# FishCaller.net
KiCad netlist of a schematic drawn in EAGLE
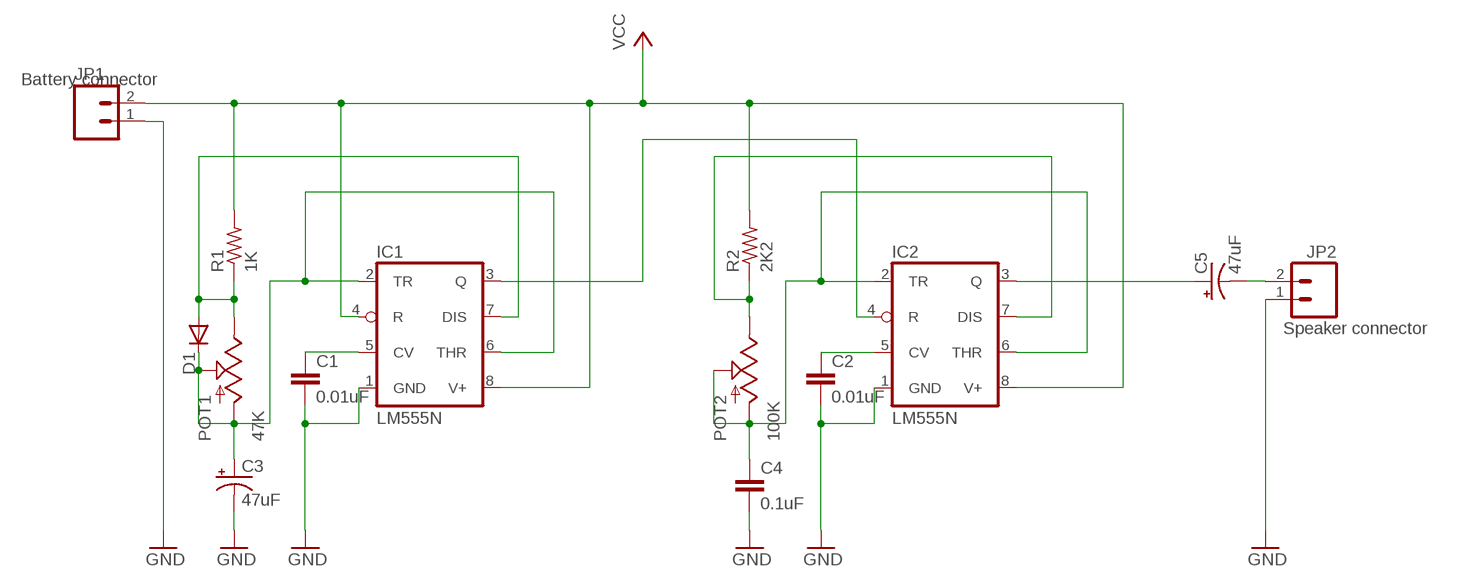
[diagram p0: schematic, sheet 1]

(export (version "E")
  (design (tool "Eeschema 10.0.6"))
  (components
    (comp (ref "C1")
      (value "0.01uF")
      (footprint "eagle-import:CAP-PTH-SMALL")
      (libsource (lib "eagle-import") (part "CAPPTH"))
    )
    (comp (ref "C2")
      (value "0.01uF")
      (footprint "eagle-import:CAP-PTH-SMALL")
      (libsource (lib "eagle-import") (part "CAPPTH"))
    )
    (comp (ref "C3")
      (value "47uF")
      (footprint "eagle-import:E2,5-6")
      (libsource (lib "eagle-import") (part "CPOL-USE2.5-6"))
    )
    (comp (ref "C4")
      (value "0.1uF")
      (footprint "eagle-import:CAP-PTH-SMALL")
      (libsource (lib "eagle-import") (part "CAPPTH"))
    )
    (comp (ref "C5")
      (value "47uF")
      (footprint "eagle-import:E2,5-6")
      (libsource (lib "eagle-import") (part "CPOL-USE2.5-6"))
    )
    (comp (ref "D1")
      (value "DIODE1N4148")
      (footprint "eagle-import:DIODE-1N4148")
      (libsource (lib "eagle-import") (part "DIODE1N4148"))
    )
    (comp (ref "IC1")
      (value "LM555N")
      (footprint "eagle-import:DIL08-ROUND")
      (libsource (lib "eagle-import") (part "555NLM"))
    )
    (comp (ref "IC2")
      (value "LM555N")
      (footprint "eagle-import:DIL08-ROUND")
      (libsource (lib "eagle-import") (part "555NLM"))
    )
    (comp (ref "JP1")
      (value "M02")
      (footprint "eagle-import:1X02_LONGPADS")
      (libsource (lib "eagle-import") (part "M02"))
    )
    (comp (ref "JP2")
      (value "M02")
      (footprint "eagle-import:1X02_LONGPADS")
      (libsource (lib "eagle-import") (part "M02"))
    )
    (comp (ref "POT1")
      (value "47K")
      (footprint "eagle-import:ALPS_POT")
      (libsource (lib "eagle-import") (part "POT"))
    )
    (comp (ref "POT2")
      (value "100K")
      (footprint "eagle-import:ALPS_POT")
      (libsource (lib "eagle-import") (part "POT"))
    )
    (comp (ref "R1")
      (value "1K")
      (footprint "eagle-import:0207_9")
      (libsource (lib "eagle-import") (part "R-US_0207/9"))
    )
    (comp (ref "R2")
      (value "2K2")
      (footprint "eagle-import:0207_9")
      (libsource (lib "eagle-import") (part "R-US_0207/9"))
    )
  )
  (nets
    (net (code "1") (name "GND") (class "Default")
      (node (ref "C1") (pin "2") (pinfunction "2_2") (pintype "passive"))
      (node (ref "C2") (pin "2") (pinfunction "2_2") (pintype "passive"))
      (node (ref "C3") (pin "-") (pinfunction "-_-") (pintype "passive"))
      (node (ref "C4") (pin "2") (pinfunction "2_2") (pintype "passive"))
      (node (ref "IC1") (pin "1") (pinfunction "GND_1") (pintype "power_in"))
      (node (ref "IC2") (pin "1") (pinfunction "GND_1") (pintype "power_in"))
      (node (ref "JP1") (pin "1") (pinfunction "1_1") (pintype "passive"))
      (node (ref "JP2") (pin "1") (pinfunction "1_1") (pintype "passive"))
    )
    (net (code "2") (name "Net-(C5-Pad-)") (class "Default")
      (node (ref "C5") (pin "-") (pinfunction "-_-") (pintype "passive"))
      (node (ref "JP2") (pin "2") (pinfunction "2_2") (pintype "passive"))
    )
    (net (code "3") (name "Net-(IC1-CV)") (class "Default")
      (node (ref "C1") (pin "1") (pinfunction "1_1") (pintype "passive"))
      (node (ref "IC1") (pin "5") (pinfunction "CV_5") (pintype "input"))
    )
    (net (code "4") (name "Net-(IC1-DIS)") (class "Default")
      (node (ref "D1") (pin "A") (pinfunction "A_A") (pintype "passive"))
      (node (ref "IC1") (pin "7") (pinfunction "DIS_7") (pintype "input"))
      (node (ref "POT1") (pin "P$1") (pinfunction "E_P$1") (pintype "passive"))
      (node (ref "R1") (pin "1") (pinfunction "1_1") (pintype "passive"))
    )
    (net (code "5") (name "Net-(IC1-Q)") (class "Default")
      (node (ref "IC1") (pin "3") (pinfunction "Q_3") (pintype "output"))
      (node (ref "IC2") (pin "4") (pinfunction "R_4") (pintype "input"))
    )
    (net (code "6") (name "Net-(IC1-THR)") (class "Default")
      (node (ref "C3") (pin "+") (pinfunction "+_+") (pintype "passive"))
      (node (ref "D1") (pin "C") (pinfunction "C_C") (pintype "passive"))
      (node (ref "IC1") (pin "2") (pinfunction "TR_2") (pintype "input"))
      (node (ref "IC1") (pin "6") (pinfunction "THR_6") (pintype "input"))
      (node (ref "POT1") (pin "P$2") (pinfunction "S_P$2") (pintype "passive"))
      (node (ref "POT1") (pin "P$3") (pinfunction "A_P$3") (pintype "passive"))
    )
    (net (code "7") (name "Net-(IC2-CV)") (class "Default")
      (node (ref "C2") (pin "1") (pinfunction "1_1") (pintype "passive"))
      (node (ref "IC2") (pin "5") (pinfunction "CV_5") (pintype "input"))
    )
    (net (code "8") (name "Net-(IC2-DIS)") (class "Default")
      (node (ref "IC2") (pin "7") (pinfunction "DIS_7") (pintype "input"))
      (node (ref "POT2") (pin "P$1") (pinfunction "E_P$1") (pintype "passive"))
      (node (ref "R2") (pin "1") (pinfunction "1_1") (pintype "passive"))
    )
    (net (code "9") (name "Net-(IC2-Q)") (class "Default")
      (node (ref "C5") (pin "+") (pinfunction "+_+") (pintype "passive"))
      (node (ref "IC2") (pin "3") (pinfunction "Q_3") (pintype "output"))
    )
    (net (code "10") (name "Net-(IC2-THR)") (class "Default")
      (node (ref "C4") (pin "1") (pinfunction "1_1") (pintype "passive"))
      (node (ref "IC2") (pin "2") (pinfunction "TR_2") (pintype "input"))
      (node (ref "IC2") (pin "6") (pinfunction "THR_6") (pintype "input"))
      (node (ref "POT2") (pin "P$2") (pinfunction "S_P$2") (pintype "passive"))
      (node (ref "POT2") (pin "P$3") (pinfunction "A_P$3") (pintype "passive"))
    )
    (net (code "11") (name "VCC") (class "Default")
      (node (ref "IC1") (pin "4") (pinfunction "R_4") (pintype "input"))
      (node (ref "IC1") (pin "8") (pinfunction "V+_8") (pintype "power_in"))
      (node (ref "IC2") (pin "8") (pinfunction "V+_8") (pintype "power_in"))
      (node (ref "JP1") (pin "2") (pinfunction "2_2") (pintype "passive"))
      (node (ref "R1") (pin "2") (pinfunction "2_2") (pintype "passive"))
      (node (ref "R2") (pin "2") (pinfunction "2_2") (pintype "passive"))
    )
  )
)
